# bbb_blk.net
KiCad netlist of a schematic drawn in Altium Designer
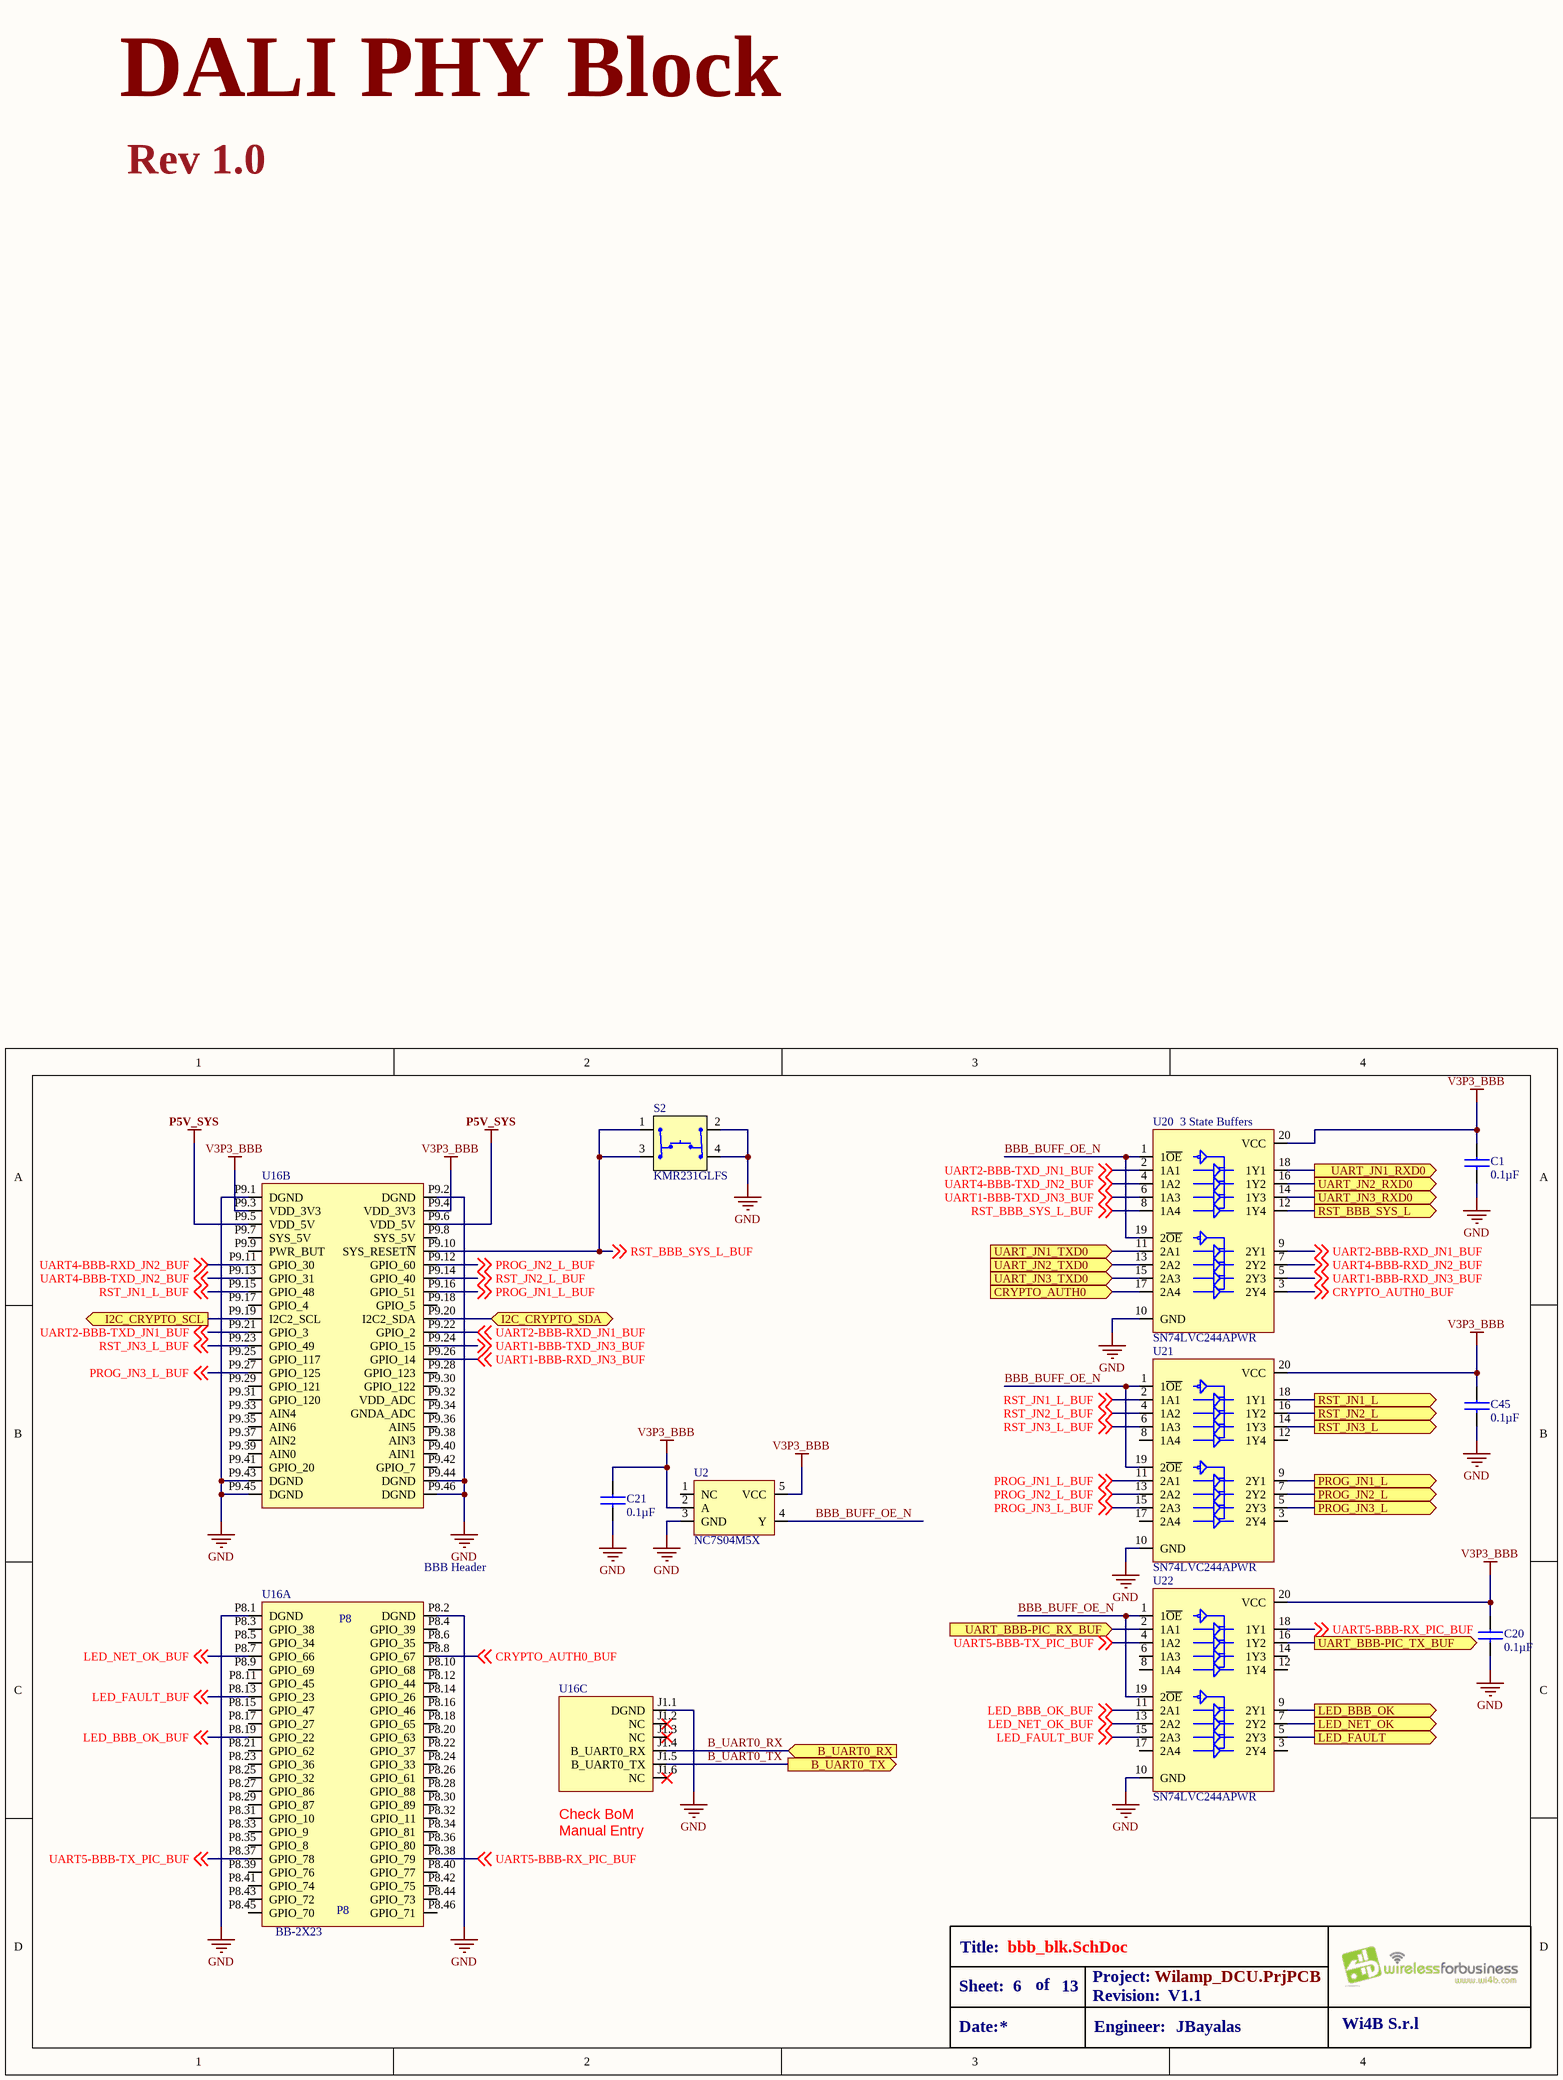
[diagram p0: bbb_blk.SchDoc]

(export (version "E")
  (design (tool "Eeschema 10.0.6"))
  (components
    (comp (ref "C1")
      (value "0.1µF")
      (footprint "C0402")
      (description "CAP CER 0.1UF 16V X7R 0402")
      (fields (field (name "MPN") "CL05B104KO3LNNC"))
      (libsource (lib "Capacitor") (part "CL05B104KO3LNNC"))
    )
    (comp (ref "C20")
      (value "0.1µF")
      (footprint "C0402")
      (description "CAP CER 0.1UF 16V X7R 0402")
      (fields (field (name "MPN") "CL05B104KO3LNNC"))
      (libsource (lib "Capacitor") (part "CL05B104KO3LNNC"))
    )
    (comp (ref "C21")
      (value "0.1µF")
      (footprint "C0402")
      (description "CAP CER 0.1UF 16V X7R 0402")
      (fields (field (name "MPN") "CL05B104KO3LNNC"))
      (libsource (lib "Capacitor") (part "CL05B104KO3LNNC"))
    )
    (comp (ref "C45")
      (value "0.1µF")
      (footprint "C0402")
      (description "CAP CER 0.1UF 16V X7R 0402")
      (fields (field (name "MPN") "CL05B104KO3LNNC"))
      (libsource (lib "Capacitor") (part "CL05B104KO3LNNC"))
    )
    (comp (ref "S2")
      (value "*")
      (footprint "KMR231G ULC LFS")
      (description "SWITCH TACTILE SPST-NO 0.05A 32V")
      (fields (field (name "MPN") "KMR231GLFS"))
      (libsource (lib "Switch") (part "KMR231GLFS"))
    )
    (comp (ref "U2")
      (value "*")
      (footprint "SOT 23-5")
      (description "IC INVERTER HS SINGLE SOT-23-5")
      (fields (field (name "MPN") "NC7S04M5X"))
      (libsource (lib "IC") (part "NC7S04M5X"))
    )
    (comp (ref "U16")
      (value "BEAGLE_BONE_BLACK_CAPE")
      (footprint "BEAGLE_BONE_BLACK_CAPE")
      (description "Beaglebone 2x23 Pin stacking header(2 Pack )")
      (fields (field (name "MPN") "BB-2X23"))
      (libsource (lib "") (part "BEAGLE_BONE_BLACK_CAPE_1"))
    )
    (comp (ref "U20")
      (value "SN74LVC244APWR")
      (footprint "TSSOP-20 (SN74LVC)")
      (description "IC BUFF/DVR TRI-ST DUAL 20TSSOP")
      (libsource (lib "IC") (part "SN74LVC244APWR"))
    )
    (comp (ref "U21")
      (value "SN74LVC244APWR")
      (footprint "TSSOP-20 (SN74LVC)")
      (description "IC BUFF/DVR TRI-ST DUAL 20TSSOP")
      (libsource (lib "IC") (part "SN74LVC244APWR"))
    )
    (comp (ref "U22")
      (value "SN74LVC244APWR")
      (footprint "TSSOP-20 (SN74LVC)")
      (description "IC BUFF/DVR TRI-ST DUAL 20TSSOP")
      (libsource (lib "IC") (part "SN74LVC244APWR"))
    )
  )
  (nets
    (net (code "1") (name "/BBB_BUFF_OE_N") (class "Default")
      (node (ref "U2") (pin "4") (pinfunction "Y_4") (pintype "passive"))
      (node (ref "U20") (pin "1") (pinfunction "1~{OE}_1") (pintype "passive"))
      (node (ref "U20") (pin "19") (pinfunction "2~{OE}_19") (pintype "passive"))
      (node (ref "U21") (pin "1") (pinfunction "1~{OE}_1") (pintype "passive"))
      (node (ref "U21") (pin "19") (pinfunction "2~{OE}_19") (pintype "passive"))
      (node (ref "U22") (pin "1") (pinfunction "1~{OE}_1") (pintype "passive"))
      (node (ref "U22") (pin "19") (pinfunction "2~{OE}_19") (pintype "passive"))
    )
    (net (code "2") (name "/B_UART0_RX") (class "Default")
      (node (ref "U16") (pin "J1.4") (pinfunction "B_UART0_RX_J1.4") (pintype "passive"))
    )
    (net (code "3") (name "/B_UART0_TX") (class "Default")
      (node (ref "U16") (pin "J1.5") (pinfunction "B_UART0_TX_J1.5") (pintype "passive"))
    )
    (net (code "4") (name "/CRYPTO_AUTH0") (class "Default")
      (node (ref "U20") (pin "17") (pinfunction "2A4_17") (pintype "passive"))
    )
    (net (code "5") (name "/I2C_CRYPTO_SCL") (class "Default")
      (node (ref "U16") (pin "P9.19") (pinfunction "I2C2_SCL_P9.19") (pintype "passive"))
    )
    (net (code "6") (name "/I2C_CRYPTO_SDA") (class "Default")
      (node (ref "U16") (pin "P9.20") (pinfunction "I2C2_SDA_P9.20") (pintype "passive"))
    )
    (net (code "7") (name "/LED_BBB_OK") (class "Default")
      (node (ref "U22") (pin "9") (pinfunction "2Y1_9") (pintype "passive"))
    )
    (net (code "8") (name "/LED_FAULT") (class "Default")
      (node (ref "U22") (pin "5") (pinfunction "2Y3_5") (pintype "passive"))
    )
    (net (code "9") (name "/LED_NET_OK") (class "Default")
      (node (ref "U22") (pin "7") (pinfunction "2Y2_7") (pintype "passive"))
    )
    (net (code "10") (name "/PROG_JN1_L") (class "Default")
      (node (ref "U21") (pin "9") (pinfunction "2Y1_9") (pintype "passive"))
    )
    (net (code "11") (name "/PROG_JN2_L") (class "Default")
      (node (ref "U21") (pin "7") (pinfunction "2Y2_7") (pintype "passive"))
    )
    (net (code "12") (name "/PROG_JN3_L") (class "Default")
      (node (ref "U21") (pin "5") (pinfunction "2Y3_5") (pintype "passive"))
    )
    (net (code "13") (name "/RST_BBB_SYS_L") (class "Default")
      (node (ref "U20") (pin "12") (pinfunction "1Y4_12") (pintype "passive"))
    )
    (net (code "14") (name "/RST_JN1_L") (class "Default")
      (node (ref "U21") (pin "18") (pinfunction "1Y1_18") (pintype "passive"))
    )
    (net (code "15") (name "/RST_JN2_L") (class "Default")
      (node (ref "U21") (pin "16") (pinfunction "1Y2_16") (pintype "passive"))
    )
    (net (code "16") (name "/RST_JN3_L") (class "Default")
      (node (ref "U21") (pin "14") (pinfunction "1Y3_14") (pintype "passive"))
    )
    (net (code "17") (name "/UART_BBB-PIC_RX_BUF") (class "Default")
      (node (ref "U22") (pin "2") (pinfunction "1A1_2") (pintype "passive"))
    )
    (net (code "18") (name "/UART_BBB-PIC_TX_BUF") (class "Default")
      (node (ref "U22") (pin "16") (pinfunction "1Y2_16") (pintype "passive"))
    )
    (net (code "19") (name "/UART_JN1_RXD0") (class "Default")
      (node (ref "U20") (pin "18") (pinfunction "1Y1_18") (pintype "passive"))
    )
    (net (code "20") (name "/UART_JN1_TXD0") (class "Default")
      (node (ref "U20") (pin "11") (pinfunction "2A1_11") (pintype "passive"))
    )
    (net (code "21") (name "/UART_JN2_RXD0") (class "Default")
      (node (ref "U20") (pin "16") (pinfunction "1Y2_16") (pintype "passive"))
    )
    (net (code "22") (name "/UART_JN2_TXD0") (class "Default")
      (node (ref "U20") (pin "13") (pinfunction "2A2_13") (pintype "passive"))
    )
    (net (code "23") (name "/UART_JN3_RXD0") (class "Default")
      (node (ref "U20") (pin "14") (pinfunction "1Y3_14") (pintype "passive"))
    )
    (net (code "24") (name "/UART_JN3_TXD0") (class "Default")
      (node (ref "U20") (pin "15") (pinfunction "2A3_15") (pintype "passive"))
    )
    (net (code "25") (name "CRYPTO_AUTH0_BUF") (class "Default")
      (node (ref "U16") (pin "P8.8") (pinfunction "GPIO_67_P8.8") (pintype "passive"))
      (node (ref "U20") (pin "3") (pinfunction "2Y4_3") (pintype "passive"))
    )
    (net (code "26") (name "GND") (class "Default")
      (node (ref "C1") (pin "2") (pinfunction "2_2") (pintype "passive"))
      (node (ref "C20") (pin "2") (pinfunction "2_2") (pintype "passive"))
      (node (ref "C21") (pin "2") (pinfunction "2_2") (pintype "passive"))
      (node (ref "C45") (pin "2") (pinfunction "2_2") (pintype "passive"))
      (node (ref "S2") (pin "2") (pinfunction "2_2") (pintype "passive"))
      (node (ref "S2") (pin "4") (pinfunction "4_4") (pintype "passive"))
      (node (ref "U16") (pin "J1.1") (pinfunction "DGND_J1.1") (pintype "passive"))
      (node (ref "U16") (pin "P8.1") (pinfunction "DGND_P8.1") (pintype "passive"))
      (node (ref "U16") (pin "P8.2") (pinfunction "DGND_P8.2") (pintype "passive"))
      (node (ref "U16") (pin "P9.1") (pinfunction "DGND_P9.1") (pintype "passive"))
      (node (ref "U16") (pin "P9.2") (pinfunction "DGND_P9.2") (pintype "passive"))
      (node (ref "U16") (pin "P9.43") (pinfunction "DGND_P9.43") (pintype "passive"))
      (node (ref "U16") (pin "P9.44") (pinfunction "DGND_P9.44") (pintype "passive"))
      (node (ref "U16") (pin "P9.45") (pinfunction "DGND_P9.45") (pintype "passive"))
      (node (ref "U16") (pin "P9.46") (pinfunction "DGND_P9.46") (pintype "passive"))
      (node (ref "U2") (pin "3") (pinfunction "GND_3") (pintype "passive"))
      (node (ref "U20") (pin "10") (pinfunction "GND_10") (pintype "passive"))
      (node (ref "U21") (pin "10") (pinfunction "GND_10") (pintype "passive"))
      (node (ref "U22") (pin "10") (pinfunction "GND_10") (pintype "passive"))
    )
    (net (code "27") (name "LED_BBB_OK_BUF") (class "Default")
      (node (ref "U16") (pin "P8.19") (pinfunction "GPIO_22_P8.19") (pintype "passive"))
      (node (ref "U22") (pin "11") (pinfunction "2A1_11") (pintype "passive"))
    )
    (net (code "28") (name "LED_FAULT_BUF") (class "Default")
      (node (ref "U16") (pin "P8.13") (pinfunction "GPIO_23_P8.13") (pintype "passive"))
      (node (ref "U22") (pin "15") (pinfunction "2A3_15") (pintype "passive"))
    )
    (net (code "29") (name "LED_NET_OK_BUF") (class "Default")
      (node (ref "U16") (pin "P8.7") (pinfunction "GPIO_66_P8.7") (pintype "passive"))
      (node (ref "U22") (pin "13") (pinfunction "2A2_13") (pintype "passive"))
    )
    (net (code "30") (name "P5V_SYS") (class "Default")
      (node (ref "U16") (pin "P9.5") (pinfunction "VDD_5V_P9.5") (pintype "passive"))
      (node (ref "U16") (pin "P9.6") (pinfunction "VDD_5V_P9.6") (pintype "passive"))
    )
    (net (code "31") (name "PROG_JN1_L_BUF") (class "Default")
      (node (ref "U16") (pin "P9.16") (pinfunction "GPIO_51_P9.16") (pintype "passive"))
      (node (ref "U21") (pin "11") (pinfunction "2A1_11") (pintype "passive"))
    )
    (net (code "32") (name "PROG_JN2_L_BUF") (class "Default")
      (node (ref "U16") (pin "P9.12") (pinfunction "GPIO_60_P9.12") (pintype "passive"))
      (node (ref "U21") (pin "13") (pinfunction "2A2_13") (pintype "passive"))
    )
    (net (code "33") (name "PROG_JN3_L_BUF") (class "Default")
      (node (ref "U16") (pin "P9.27") (pinfunction "GPIO_125_P9.27") (pintype "passive"))
      (node (ref "U21") (pin "15") (pinfunction "2A3_15") (pintype "passive"))
    )
    (net (code "34") (name "RST_BBB_SYS_L_BUF") (class "Default")
      (node (ref "S2") (pin "1") (pinfunction "1_1") (pintype "passive"))
      (node (ref "S2") (pin "3") (pinfunction "3_3") (pintype "passive"))
      (node (ref "U16") (pin "P9.10") (pinfunction "SYS_RESET~{N}_P9.10") (pintype "passive"))
      (node (ref "U20") (pin "8") (pinfunction "1A4_8") (pintype "passive"))
    )
    (net (code "35") (name "RST_JN1_L_BUF") (class "Default")
      (node (ref "U16") (pin "P9.15") (pinfunction "GPIO_48_P9.15") (pintype "passive"))
      (node (ref "U21") (pin "2") (pinfunction "1A1_2") (pintype "passive"))
    )
    (net (code "36") (name "RST_JN2_L_BUF") (class "Default")
      (node (ref "U16") (pin "P9.14") (pinfunction "GPIO_40_P9.14") (pintype "passive"))
      (node (ref "U21") (pin "4") (pinfunction "1A2_4") (pintype "passive"))
    )
    (net (code "37") (name "RST_JN3_L_BUF") (class "Default")
      (node (ref "U16") (pin "P9.23") (pinfunction "GPIO_49_P9.23") (pintype "passive"))
      (node (ref "U21") (pin "6") (pinfunction "1A3_6") (pintype "passive"))
    )
    (net (code "38") (name "UART1-BBB-RXD_JN3_BUF") (class "Default")
      (node (ref "U16") (pin "P9.26") (pinfunction "GPIO_14_P9.26") (pintype "passive"))
      (node (ref "U20") (pin "5") (pinfunction "2Y3_5") (pintype "passive"))
    )
    (net (code "39") (name "UART1-BBB-TXD_JN3_BUF") (class "Default")
      (node (ref "U16") (pin "P9.24") (pinfunction "GPIO_15_P9.24") (pintype "passive"))
      (node (ref "U20") (pin "6") (pinfunction "1A3_6") (pintype "passive"))
    )
    (net (code "40") (name "UART2-BBB-RXD_JN1_BUF") (class "Default")
      (node (ref "U16") (pin "P9.22") (pinfunction "GPIO_2_P9.22") (pintype "passive"))
      (node (ref "U20") (pin "9") (pinfunction "2Y1_9") (pintype "passive"))
    )
    (net (code "41") (name "UART2-BBB-TXD_JN1_BUF") (class "Default")
      (node (ref "U16") (pin "P9.21") (pinfunction "GPIO_3_P9.21") (pintype "passive"))
      (node (ref "U20") (pin "2") (pinfunction "1A1_2") (pintype "passive"))
    )
    (net (code "42") (name "UART4-BBB-RXD_JN2_BUF") (class "Default")
      (node (ref "U16") (pin "P9.11") (pinfunction "GPIO_30_P9.11") (pintype "passive"))
      (node (ref "U20") (pin "7") (pinfunction "2Y2_7") (pintype "passive"))
    )
    (net (code "43") (name "UART4-BBB-TXD_JN2_BUF") (class "Default")
      (node (ref "U16") (pin "P9.13") (pinfunction "GPIO_31_P9.13") (pintype "passive"))
      (node (ref "U20") (pin "4") (pinfunction "1A2_4") (pintype "passive"))
    )
    (net (code "44") (name "UART5-BBB-RX_PIC_BUF") (class "Default")
      (node (ref "U16") (pin "P8.38") (pinfunction "GPIO_79_P8.38") (pintype "passive"))
      (node (ref "U22") (pin "18") (pinfunction "1Y1_18") (pintype "passive"))
    )
    (net (code "45") (name "UART5-BBB-TX_PIC_BUF") (class "Default")
      (node (ref "U16") (pin "P8.37") (pinfunction "GPIO_78_P8.37") (pintype "passive"))
      (node (ref "U22") (pin "4") (pinfunction "1A2_4") (pintype "passive"))
    )
    (net (code "46") (name "V3P3_BBB") (class "Default")
      (node (ref "C1") (pin "1") (pinfunction "1_1") (pintype "passive"))
      (node (ref "C20") (pin "1") (pinfunction "1_1") (pintype "passive"))
      (node (ref "C21") (pin "1") (pinfunction "1_1") (pintype "passive"))
      (node (ref "C45") (pin "1") (pinfunction "1_1") (pintype "passive"))
      (node (ref "U16") (pin "P9.3") (pinfunction "VDD_3V3_P9.3") (pintype "passive"))
      (node (ref "U16") (pin "P9.4") (pinfunction "VDD_3V3_P9.4") (pintype "passive"))
      (node (ref "U2") (pin "2") (pinfunction "A_2") (pintype "passive"))
      (node (ref "U2") (pin "5") (pinfunction "VCC_5") (pintype "passive"))
      (node (ref "U20") (pin "20") (pinfunction "VCC_20") (pintype "passive"))
      (node (ref "U21") (pin "20") (pinfunction "VCC_20") (pintype "passive"))
      (node (ref "U22") (pin "20") (pinfunction "VCC_20") (pintype "passive"))
    )
    (net (code "47") (name "unconnected-(U2-NC-Pad1)") (class "Default")
      (node (ref "U2") (pin "1") (pinfunction "NC_1") (pintype "passive"))
    )
    (net (code "48") (name "unconnected-(U16A-GPIO_8-PadP8.35)") (class "Default")
      (node (ref "U16") (pin "P8.35") (pinfunction "GPIO_8_P8.35") (pintype "passive"))
    )
    (net (code "49") (name "unconnected-(U16A-GPIO_9-PadP8.33)") (class "Default")
      (node (ref "U16") (pin "P8.33") (pinfunction "GPIO_9_P8.33") (pintype "passive"))
    )
    (net (code "50") (name "unconnected-(U16A-GPIO_10-PadP8.31)") (class "Default")
      (node (ref "U16") (pin "P8.31") (pinfunction "GPIO_10_P8.31") (pintype "passive"))
    )
    (net (code "51") (name "unconnected-(U16A-GPIO_11-PadP8.32)") (class "Default")
      (node (ref "U16") (pin "P8.32") (pinfunction "GPIO_11_P8.32") (pintype "passive"))
    )
    (net (code "52") (name "unconnected-(U16A-GPIO_26-PadP8.14)") (class "Default")
      (node (ref "U16") (pin "P8.14") (pinfunction "GPIO_26_P8.14") (pintype "passive"))
    )
    (net (code "53") (name "unconnected-(U16A-GPIO_27-PadP8.17)") (class "Default")
      (node (ref "U16") (pin "P8.17") (pinfunction "GPIO_27_P8.17") (pintype "passive"))
    )
    (net (code "54") (name "unconnected-(U16A-GPIO_32-PadP8.25)") (class "Default")
      (node (ref "U16") (pin "P8.25") (pinfunction "GPIO_32_P8.25") (pintype "passive"))
    )
    (net (code "55") (name "unconnected-(U16A-GPIO_33-PadP8.24)") (class "Default")
      (node (ref "U16") (pin "P8.24") (pinfunction "GPIO_33_P8.24") (pintype "passive"))
    )
    (net (code "56") (name "unconnected-(U16A-GPIO_34-PadP8.5)") (class "Default")
      (node (ref "U16") (pin "P8.5") (pinfunction "GPIO_34_P8.5") (pintype "passive"))
    )
    (net (code "57") (name "unconnected-(U16A-GPIO_35-PadP8.6)") (class "Default")
      (node (ref "U16") (pin "P8.6") (pinfunction "GPIO_35_P8.6") (pintype "passive"))
    )
    (net (code "58") (name "unconnected-(U16A-GPIO_36-PadP8.23)") (class "Default")
      (node (ref "U16") (pin "P8.23") (pinfunction "GPIO_36_P8.23") (pintype "passive"))
    )
    (net (code "59") (name "unconnected-(U16A-GPIO_37-PadP8.22)") (class "Default")
      (node (ref "U16") (pin "P8.22") (pinfunction "GPIO_37_P8.22") (pintype "passive"))
    )
    (net (code "60") (name "unconnected-(U16A-GPIO_38-PadP8.3)") (class "Default")
      (node (ref "U16") (pin "P8.3") (pinfunction "GPIO_38_P8.3") (pintype "passive"))
    )
    (net (code "61") (name "unconnected-(U16A-GPIO_39-PadP8.4)") (class "Default")
      (node (ref "U16") (pin "P8.4") (pinfunction "GPIO_39_P8.4") (pintype "passive"))
    )
    (net (code "62") (name "unconnected-(U16A-GPIO_44-PadP8.12)") (class "Default")
      (node (ref "U16") (pin "P8.12") (pinfunction "GPIO_44_P8.12") (pintype "passive"))
    )
    (net (code "63") (name "unconnected-(U16A-GPIO_45-PadP8.11)") (class "Default")
      (node (ref "U16") (pin "P8.11") (pinfunction "GPIO_45_P8.11") (pintype "passive"))
    )
    (net (code "64") (name "unconnected-(U16A-GPIO_46-PadP8.16)") (class "Default")
      (node (ref "U16") (pin "P8.16") (pinfunction "GPIO_46_P8.16") (pintype "passive"))
    )
    (net (code "65") (name "unconnected-(U16A-GPIO_47-PadP8.15)") (class "Default")
      (node (ref "U16") (pin "P8.15") (pinfunction "GPIO_47_P8.15") (pintype "passive"))
    )
    (net (code "66") (name "unconnected-(U16A-GPIO_61-PadP8.26)") (class "Default")
      (node (ref "U16") (pin "P8.26") (pinfunction "GPIO_61_P8.26") (pintype "passive"))
    )
    (net (code "67") (name "unconnected-(U16A-GPIO_62-PadP8.21)") (class "Default")
      (node (ref "U16") (pin "P8.21") (pinfunction "GPIO_62_P8.21") (pintype "passive"))
    )
    (net (code "68") (name "unconnected-(U16A-GPIO_63-PadP8.20)") (class "Default")
      (node (ref "U16") (pin "P8.20") (pinfunction "GPIO_63_P8.20") (pintype "passive"))
    )
    (net (code "69") (name "unconnected-(U16A-GPIO_65-PadP8.18)") (class "Default")
      (node (ref "U16") (pin "P8.18") (pinfunction "GPIO_65_P8.18") (pintype "passive"))
    )
    (net (code "70") (name "unconnected-(U16A-GPIO_68-PadP8.10)") (class "Default")
      (node (ref "U16") (pin "P8.10") (pinfunction "GPIO_68_P8.10") (pintype "passive"))
    )
    (net (code "71") (name "unconnected-(U16A-GPIO_69-PadP8.9)") (class "Default")
      (node (ref "U16") (pin "P8.9") (pinfunction "GPIO_69_P8.9") (pintype "passive"))
    )
    (net (code "72") (name "unconnected-(U16A-GPIO_70-PadP8.45)") (class "Default")
      (node (ref "U16") (pin "P8.45") (pinfunction "GPIO_70_P8.45") (pintype "passive"))
    )
    (net (code "73") (name "unconnected-(U16A-GPIO_71-PadP8.46)") (class "Default")
      (node (ref "U16") (pin "P8.46") (pinfunction "GPIO_71_P8.46") (pintype "passive"))
    )
    (net (code "74") (name "unconnected-(U16A-GPIO_72-PadP8.43)") (class "Default")
      (node (ref "U16") (pin "P8.43") (pinfunction "GPIO_72_P8.43") (pintype "passive"))
    )
    (net (code "75") (name "unconnected-(U16A-GPIO_73-PadP8.44)") (class "Default")
      (node (ref "U16") (pin "P8.44") (pinfunction "GPIO_73_P8.44") (pintype "passive"))
    )
    (net (code "76") (name "unconnected-(U16A-GPIO_74-PadP8.41)") (class "Default")
      (node (ref "U16") (pin "P8.41") (pinfunction "GPIO_74_P8.41") (pintype "passive"))
    )
    (net (code "77") (name "unconnected-(U16A-GPIO_75-PadP8.42)") (class "Default")
      (node (ref "U16") (pin "P8.42") (pinfunction "GPIO_75_P8.42") (pintype "passive"))
    )
    (net (code "78") (name "unconnected-(U16A-GPIO_76-PadP8.39)") (class "Default")
      (node (ref "U16") (pin "P8.39") (pinfunction "GPIO_76_P8.39") (pintype "passive"))
    )
    (net (code "79") (name "unconnected-(U16A-GPIO_77-PadP8.40)") (class "Default")
      (node (ref "U16") (pin "P8.40") (pinfunction "GPIO_77_P8.40") (pintype "passive"))
    )
    (net (code "80") (name "unconnected-(U16A-GPIO_80-PadP8.36)") (class "Default")
      (node (ref "U16") (pin "P8.36") (pinfunction "GPIO_80_P8.36") (pintype "passive"))
    )
    (net (code "81") (name "unconnected-(U16A-GPIO_81-PadP8.34)") (class "Default")
      (node (ref "U16") (pin "P8.34") (pinfunction "GPIO_81_P8.34") (pintype "passive"))
    )
    (net (code "82") (name "unconnected-(U16A-GPIO_86-PadP8.27)") (class "Default")
      (node (ref "U16") (pin "P8.27") (pinfunction "GPIO_86_P8.27") (pintype "passive"))
    )
    (net (code "83") (name "unconnected-(U16A-GPIO_87-PadP8.29)") (class "Default")
      (node (ref "U16") (pin "P8.29") (pinfunction "GPIO_87_P8.29") (pintype "passive"))
    )
    (net (code "84") (name "unconnected-(U16A-GPIO_88-PadP8.28)") (class "Default")
      (node (ref "U16") (pin "P8.28") (pinfunction "GPIO_88_P8.28") (pintype "passive"))
    )
    (net (code "85") (name "unconnected-(U16A-GPIO_89-PadP8.30)") (class "Default")
      (node (ref "U16") (pin "P8.30") (pinfunction "GPIO_89_P8.30") (pintype "passive"))
    )
    (net (code "86") (name "unconnected-(U16B-AIN0-PadP9.39)") (class "Default")
      (node (ref "U16") (pin "P9.39") (pinfunction "AIN0_P9.39") (pintype "passive"))
    )
    (net (code "87") (name "unconnected-(U16B-AIN1-PadP9.40)") (class "Default")
      (node (ref "U16") (pin "P9.40") (pinfunction "AIN1_P9.40") (pintype "passive"))
    )
    (net (code "88") (name "unconnected-(U16B-AIN2-PadP9.37)") (class "Default")
      (node (ref "U16") (pin "P9.37") (pinfunction "AIN2_P9.37") (pintype "passive"))
    )
    (net (code "89") (name "unconnected-(U16B-AIN3-PadP9.38)") (class "Default")
      (node (ref "U16") (pin "P9.38") (pinfunction "AIN3_P9.38") (pintype "passive"))
    )
    (net (code "90") (name "unconnected-(U16B-AIN4-PadP9.33)") (class "Default")
      (node (ref "U16") (pin "P9.33") (pinfunction "AIN4_P9.33") (pintype "passive"))
    )
    (net (code "91") (name "unconnected-(U16B-AIN5-PadP9.36)") (class "Default")
      (node (ref "U16") (pin "P9.36") (pinfunction "AIN5_P9.36") (pintype "passive"))
    )
    (net (code "92") (name "unconnected-(U16B-AIN6-PadP9.35)") (class "Default")
      (node (ref "U16") (pin "P9.35") (pinfunction "AIN6_P9.35") (pintype "passive"))
    )
    (net (code "93") (name "unconnected-(U16B-GNDA_ADC-PadP9.34)") (class "Default")
      (node (ref "U16") (pin "P9.34") (pinfunction "GNDA_ADC_P9.34") (pintype "passive"))
    )
    (net (code "94") (name "unconnected-(U16B-GPIO_4-PadP9.17)") (class "Default")
      (node (ref "U16") (pin "P9.17") (pinfunction "GPIO_4_P9.17") (pintype "passive"))
    )
    (net (code "95") (name "unconnected-(U16B-GPIO_5-PadP9.18)") (class "Default")
      (node (ref "U16") (pin "P9.18") (pinfunction "GPIO_5_P9.18") (pintype "passive"))
    )
    (net (code "96") (name "unconnected-(U16B-GPIO_7-PadP9.42)") (class "Default")
      (node (ref "U16") (pin "P9.42") (pinfunction "GPIO_7_P9.42") (pintype "passive"))
    )
    (net (code "97") (name "unconnected-(U16B-GPIO_20-PadP9.41)") (class "Default")
      (node (ref "U16") (pin "P9.41") (pinfunction "GPIO_20_P9.41") (pintype "passive"))
    )
    (net (code "98") (name "unconnected-(U16B-GPIO_117-PadP9.25)") (class "Default")
      (node (ref "U16") (pin "P9.25") (pinfunction "GPIO_117_P9.25") (pintype "passive"))
    )
    (net (code "99") (name "unconnected-(U16B-GPIO_120-PadP9.31)") (class "Default")
      (node (ref "U16") (pin "P9.31") (pinfunction "GPIO_120_P9.31") (pintype "passive"))
    )
    (net (code "100") (name "unconnected-(U16B-GPIO_121-PadP9.29)") (class "Default")
      (node (ref "U16") (pin "P9.29") (pinfunction "GPIO_121_P9.29") (pintype "passive"))
    )
    (net (code "101") (name "unconnected-(U16B-GPIO_122-PadP9.30)") (class "Default")
      (node (ref "U16") (pin "P9.30") (pinfunction "GPIO_122_P9.30") (pintype "passive"))
    )
    (net (code "102") (name "unconnected-(U16B-GPIO_123-PadP9.28)") (class "Default")
      (node (ref "U16") (pin "P9.28") (pinfunction "GPIO_123_P9.28") (pintype "passive"))
    )
    (net (code "103") (name "unconnected-(U16B-PWR_BUT-PadP9.9)") (class "Default")
      (node (ref "U16") (pin "P9.9") (pinfunction "PWR_BUT_P9.9") (pintype "passive"))
    )
    (net (code "104") (name "unconnected-(U16B-SYS_5V-PadP9.7)") (class "Default")
      (node (ref "U16") (pin "P9.7") (pinfunction "SYS_5V_P9.7") (pintype "passive"))
    )
    (net (code "105") (name "unconnected-(U16B-SYS_5V-PadP9.8)") (class "Default")
      (node (ref "U16") (pin "P9.8") (pinfunction "SYS_5V_P9.8") (pintype "passive"))
    )
    (net (code "106") (name "unconnected-(U16B-VDD_ADC-PadP9.32)") (class "Default")
      (node (ref "U16") (pin "P9.32") (pinfunction "VDD_ADC_P9.32") (pintype "passive"))
    )
    (net (code "107") (name "unconnected-(U16C-NC-PadJ1.2)") (class "Default")
      (node (ref "U16") (pin "J1.2") (pinfunction "NC_J1.2") (pintype "passive+no_connect"))
    )
    (net (code "108") (name "unconnected-(U16C-NC-PadJ1.3)") (class "Default")
      (node (ref "U16") (pin "J1.3") (pinfunction "NC_J1.3") (pintype "passive+no_connect"))
    )
    (net (code "109") (name "unconnected-(U16C-NC-PadJ1.6)") (class "Default")
      (node (ref "U16") (pin "J1.6") (pinfunction "NC_J1.6") (pintype "passive+no_connect"))
    )
    (net (code "110") (name "unconnected-(U21-1A4-Pad8)") (class "Default")
      (node (ref "U21") (pin "8") (pinfunction "1A4_8") (pintype "passive"))
    )
    (net (code "111") (name "unconnected-(U21-1Y4-Pad12)") (class "Default")
      (node (ref "U21") (pin "12") (pinfunction "1Y4_12") (pintype "passive"))
    )
    (net (code "112") (name "unconnected-(U21-2A4-Pad17)") (class "Default")
      (node (ref "U21") (pin "17") (pinfunction "2A4_17") (pintype "passive"))
    )
    (net (code "113") (name "unconnected-(U21-2Y4-Pad3)") (class "Default")
      (node (ref "U21") (pin "3") (pinfunction "2Y4_3") (pintype "passive"))
    )
    (net (code "114") (name "unconnected-(U22-1A3-Pad6)") (class "Default")
      (node (ref "U22") (pin "6") (pinfunction "1A3_6") (pintype "passive"))
    )
    (net (code "115") (name "unconnected-(U22-1A4-Pad8)") (class "Default")
      (node (ref "U22") (pin "8") (pinfunction "1A4_8") (pintype "passive"))
    )
    (net (code "116") (name "unconnected-(U22-1Y3-Pad14)") (class "Default")
      (node (ref "U22") (pin "14") (pinfunction "1Y3_14") (pintype "passive"))
    )
    (net (code "117") (name "unconnected-(U22-1Y4-Pad12)") (class "Default")
      (node (ref "U22") (pin "12") (pinfunction "1Y4_12") (pintype "passive"))
    )
    (net (code "118") (name "unconnected-(U22-2A4-Pad17)") (class "Default")
      (node (ref "U22") (pin "17") (pinfunction "2A4_17") (pintype "passive"))
    )
    (net (code "119") (name "unconnected-(U22-2Y4-Pad3)") (class "Default")
      (node (ref "U22") (pin "3") (pinfunction "2Y4_3") (pintype "passive"))
    )
  )
)
